# Power.net
KiCad netlist of a schematic drawn in Altium Designer
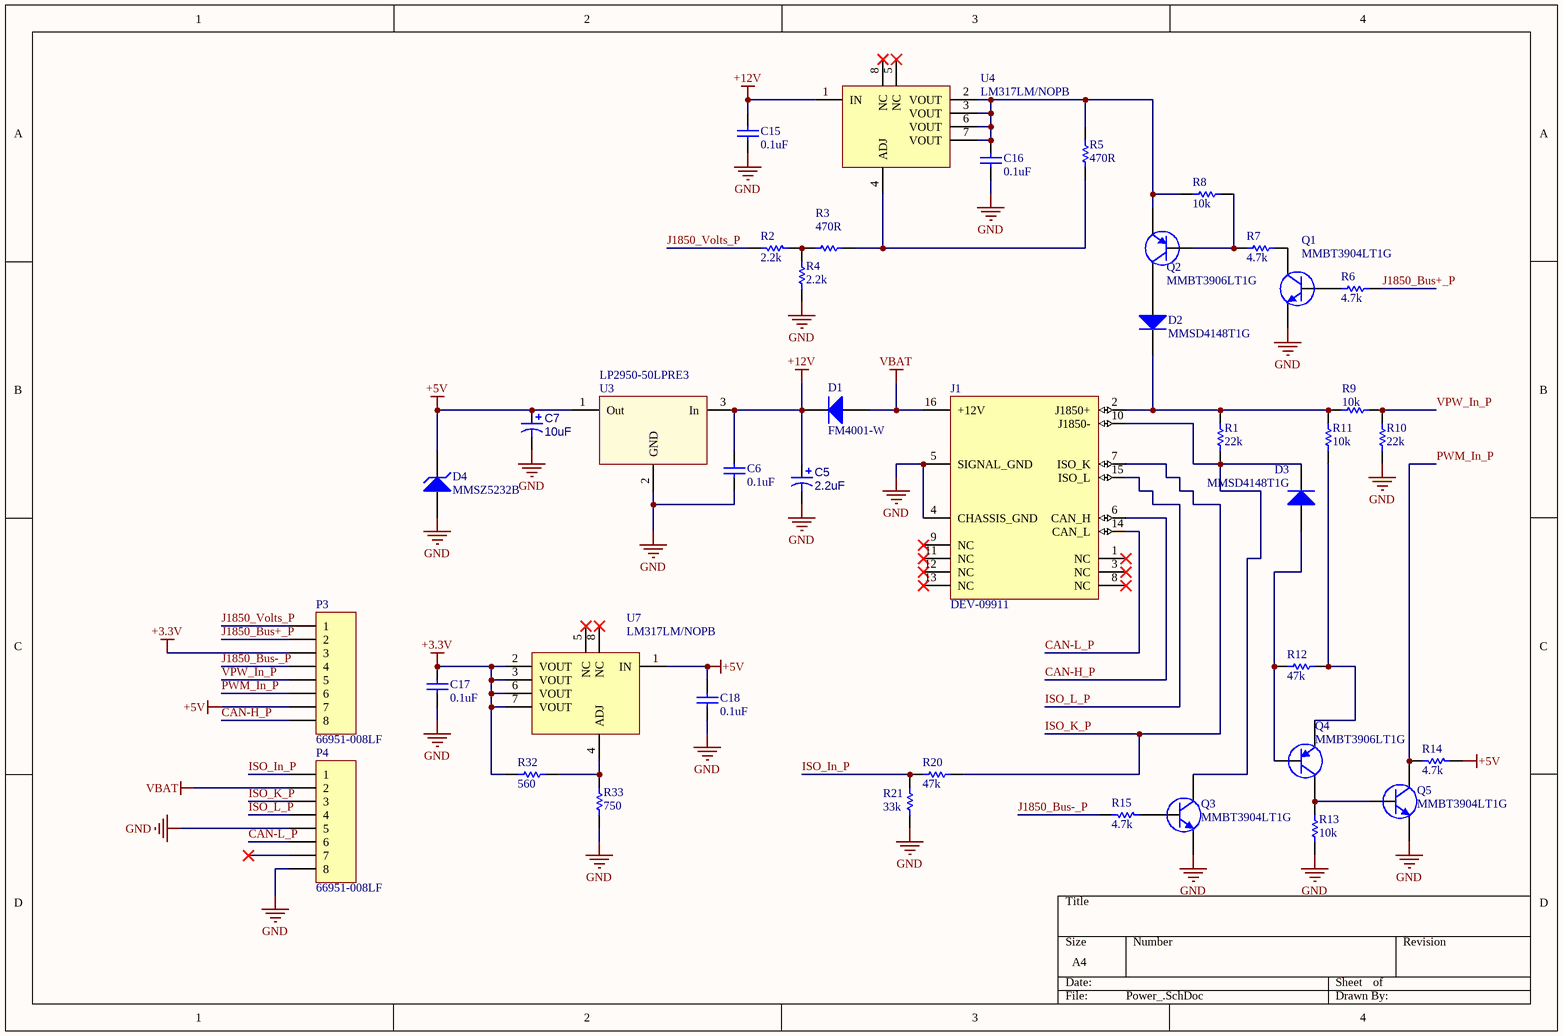
[diagram p0: Power_.SchDoc]

(export (version "E")
  (design (tool "Eeschema 10.0.6"))
  (components
    (comp (ref "C5")
      (value "2.2uF")
      (footprint "Panasonic_Ñ")
      (description "CAP ELECT 2.2UF SV 50V SMD")
      (fields (field (name "MANUFACTURER") "Panasonic") (field (name "PARTNUMBER") "EEE-1HA2R2NR"))
      (libsource (lib "OBDII-components") (part "EEE-1HA2R2NR"))
    )
    (comp (ref "C6")
      (value "0.1uF")
      (footprint "1608[0603]")
      (description "Surface-Mount Ceramic Multilayer Capacitor, 0.1uF, 10% Tolerance, 0603 Size, 50V")
      (libsource (lib "OBDII-components") (part "C0603C104K5RACTU"))
    )
    (comp (ref "C7")
      (value "10uF")
      (footprint "Panasonic_B")
      (description "CAP ELECT 10UF SV 10V SMD")
      (fields (field (name "MANUFACTURER") "Panasonic") (field (name "PARTNUMBER") "EEE-1AA100NR"))
      (libsource (lib "OBDII-components") (part "EEE-1AA100NR"))
    )
    (comp (ref "C15")
      (value "0.1uF")
      (footprint "1608[0603]")
      (description "Surface-Mount Ceramic Multilayer Capacitor, 0.1uF, X7R, 10% Tolerance, 0603 Size, 25V")
      (fields (field (name "PUBLISHER") "Altium Limited"))
      (libsource (lib "OBDII-components") (part "CGA3E2X7R1E104K080AA"))
    )
    (comp (ref "C16")
      (value "0.1uF")
      (footprint "1608[0603]")
      (description "Surface-Mount Ceramic Multilayer Capacitor, 0.1uF, X7R, 10% Tolerance, 0603 Size, 25V")
      (fields (field (name "PUBLISHER") "Altium Limited"))
      (libsource (lib "OBDII-components") (part "CGA3E2X7R1E104K080AA"))
    )
    (comp (ref "C17")
      (value "0.1uF")
      (footprint "1608[0603]")
      (description "Surface-Mount Ceramic Multilayer Capacitor, 0.1uF, 10% Tolerance, 0603 Size, 50V")
      (libsource (lib "OBDII-components") (part "C0603C104K5RACTU"))
    )
    (comp (ref "C18")
      (value "0.1uF")
      (footprint "1608[0603]")
      (description "Surface-Mount Ceramic Multilayer Capacitor, 0.1uF, 10% Tolerance, 0603 Size, 50V")
      (libsource (lib "OBDII-components") (part "C0603C104K5RACTU"))
    )
    (comp (ref "D1")
      (value "FM4001-W")
      (footprint "SMA,2.8mm")
      (description "1 Amp 50V  Rectifier")
      (libsource (lib "OBDII-components") (part "FM4001-W"))
    )
    (comp (ref "D2")
      (value "MMSD4148T1G")
      (footprint "SOD123")
      (description "High Conductance Fast Diode")
      (fields
        (field (name "MANUFACTURER") "OnSemi")
        (field (name "PUBLISHER") "Vanteon")
        (field (name "APPROVED") "M. Jablonski")
      )
      (libsource (lib "OBDII-components") (part "MMSD4148T1G"))
    )
    (comp (ref "D3")
      (value "MMSD4148T1G")
      (footprint "SOD123")
      (description "High Conductance Fast Diode")
      (fields
        (field (name "MANUFACTURER") "OnSemi")
        (field (name "PUBLISHER") "Vanteon")
        (field (name "APPROVED") "M. Jablonski")
      )
      (libsource (lib "OBDII-components") (part "MMSD4148T1G"))
    )
    (comp (ref "D4")
      (value "MMSZ5232B")
      (footprint "SOD123")
      (description "Zener Diodes 5.6 Volt 0.5W 5%")
      (libsource (lib "OBDII-components") (part "MMSZ5232B"))
    )
    (comp (ref "J1")
      (value "DEV-09911")
      (footprint "DEV-09911 - II")
      (description "OBD-II Connector")
      (fields (field (name "MANUFACTURER") "SparkFun Electronics"))
      (libsource (lib "OBDII-components") (part "OBDII_DEV-09911"))
    )
    (comp (ref "P3")
      (value "66951-008LF")
      (footprint "HDR1X8")
      (description "Connector, 8-Pin, 2.54 pitch, 1 row")
      (fields (field (name "PUBLISHER") "Altium Limited"))
      (libsource (lib "OBDII-components") (part "66951-008LF"))
    )
    (comp (ref "P4")
      (value "66951-008LF")
      (footprint "HDR1X8")
      (description "Connector, 8-Pin, 2.54 pitch, 1 row")
      (fields (field (name "PUBLISHER") "Altium Limited"))
      (libsource (lib "OBDII-components") (part "66951-008LF"))
    )
    (comp (ref "Q1")
      (value "MMBT3904LT1G")
      (footprint "SOT23")
      (description "NPN 3904 General Purpose Amplifier")
      (fields
        (field (name "MANUFACTURER") "ON Semiconductor")
        (field (name "PUBLISHER") "Vanteon")
        (field (name "APPROVED") "Yes by Implemenation")
      )
      (libsource (lib "OBDII-components") (part "MMBT3904L"))
    )
    (comp (ref "Q2")
      (value "MMBT3906LT1G")
      (footprint "SOT23")
      (description "PNP 3906 General Purpose Amplifier")
      (fields
        (field (name "MANUFACTURER") "ON Semiconductor")
        (field (name "PUBLISHER") "Vanteon")
        (field (name "APPROVED") "Yes by Implemenation")
      )
      (libsource (lib "OBDII-components") (part "MMBT3906L"))
    )
    (comp (ref "Q3")
      (value "MMBT3904LT1G")
      (footprint "SOT23")
      (description "NPN 3904 General Purpose Amplifier")
      (fields
        (field (name "MANUFACTURER") "ON Semiconductor")
        (field (name "PUBLISHER") "Vanteon")
        (field (name "APPROVED") "Yes by Implemenation")
      )
      (libsource (lib "OBDII-components") (part "MMBT3904L"))
    )
    (comp (ref "Q4")
      (value "MMBT3906LT1G")
      (footprint "SOT23")
      (description "PNP 3906 General Purpose Amplifier")
      (fields
        (field (name "MANUFACTURER") "ON Semiconductor")
        (field (name "PUBLISHER") "Vanteon")
        (field (name "APPROVED") "Yes by Implemenation")
      )
      (libsource (lib "OBDII-components") (part "MMBT3906L"))
    )
    (comp (ref "Q5")
      (value "MMBT3904LT1G")
      (footprint "SOT23")
      (description "NPN 3904 General Purpose Amplifier")
      (fields
        (field (name "MANUFACTURER") "ON Semiconductor")
        (field (name "PUBLISHER") "Vanteon")
        (field (name "APPROVED") "Yes by Implemenation")
      )
      (libsource (lib "OBDII-components") (part "MMBT3904L"))
    )
    (comp (ref "R1")
      (value "22k")
      (footprint "ERA-0805")
      (description "Rectangular Thick Film Chip Resistor, 22 kOhm, 0.1% Tolerance, 0805 Size, 0.125 W")
      (libsource (lib "OBDII-components") (part "ERA6AEB223V"))
    )
    (comp (ref "R2")
      (value "2.2k")
      (footprint "ERA-0805")
      (description "Rectangular Thick Film Chip Resistor, 2.2 kOhm, 0.1% Tolerance, 0805 Size, 0.125 W")
      (libsource (lib "OBDII-components") (part "ERA6AEB222V"))
    )
    (comp (ref "R3")
      (value "470R")
      (footprint "ERA-0805")
      (description "Rectangular Thick Film Chip Resistor, 470 Ohm, 0.1% Tolerance, 0805 Size, 0.125 W")
      (libsource (lib "OBDII-components") (part "ERA6AEB471V"))
    )
    (comp (ref "R4")
      (value "2.2k")
      (footprint "ERA-0805")
      (description "Rectangular Thick Film Chip Resistor, 2.2 kOhm, 0.1% Tolerance, 0805 Size, 0.125 W")
      (libsource (lib "OBDII-components") (part "ERA6AEB222V"))
    )
    (comp (ref "R5")
      (value "470R")
      (footprint "ERA-0805")
      (description "Rectangular Thick Film Chip Resistor, 470 Ohm, 0.1% Tolerance, 0805 Size, 0.125 W")
      (libsource (lib "OBDII-components") (part "ERA6AEB471V"))
    )
    (comp (ref "R6")
      (value "4.7k")
      (footprint "ERA-0805")
      (description "Rectangular Thick Film Chip Resistor, 4.7 kOhm, 0.1% Tolerance, 0805 Size, 0.125 W")
      (libsource (lib "OBDII-components") (part "ERA6AEB472V"))
    )
    (comp (ref "R7")
      (value "4.7k")
      (footprint "ERA-0805")
      (description "Rectangular Thick Film Chip Resistor, 4.7 kOhm, 0.1% Tolerance, 0805 Size, 0.125 W")
      (libsource (lib "OBDII-components") (part "ERA6AEB472V"))
    )
    (comp (ref "R8")
      (value "10k")
      (footprint "ERA-0805")
      (description "Rectangular Thick Film Chip Resistor, 10 kOhm, 0.1% Tolerance, 0805 Size, 0.125 W")
      (libsource (lib "OBDII-components") (part "ERA6AEB103V"))
    )
    (comp (ref "R9")
      (value "10k")
      (footprint "ERA-0805")
      (description "Rectangular Thick Film Chip Resistor, 10 kOhm, 0.1% Tolerance, 0805 Size, 0.125 W")
      (libsource (lib "OBDII-components") (part "ERA6AEB103V"))
    )
    (comp (ref "R10")
      (value "22k")
      (footprint "ERA-0805")
      (description "Rectangular Thick Film Chip Resistor, 22 kOhm, 0.1% Tolerance, 0805 Size, 0.125 W")
      (libsource (lib "OBDII-components") (part "ERA6AEB223V"))
    )
    (comp (ref "R11")
      (value "10k")
      (footprint "ERA-0805")
      (description "Rectangular Thick Film Chip Resistor, 10 kOhm, 0.1% Tolerance, 0805 Size, 0.125 W")
      (libsource (lib "OBDII-components") (part "ERA6AEB103V"))
    )
    (comp (ref "R12")
      (value "47k")
      (footprint "ERA-0805")
      (description "Rectangular Thick Film Chip Resistor, 47 kOhm, 0.1% Tolerance, 0805 Size, 0.125 W")
      (libsource (lib "OBDII-components") (part "ERA6AEB473V"))
    )
    (comp (ref "R13")
      (value "10k")
      (footprint "ERA-0805")
      (description "Rectangular Thick Film Chip Resistor, 10 kOhm, 0.1% Tolerance, 0805 Size, 0.125 W")
      (libsource (lib "OBDII-components") (part "ERA6AEB103V"))
    )
    (comp (ref "R14")
      (value "4.7k")
      (footprint "ERA-0805")
      (description "Rectangular Thick Film Chip Resistor, 4.7 kOhm, 0.1% Tolerance, 0805 Size, 0.125 W")
      (libsource (lib "OBDII-components") (part "ERA6AEB472V"))
    )
    (comp (ref "R15")
      (value "4.7k")
      (footprint "ERA-0805")
      (description "Rectangular Thick Film Chip Resistor, 4.7 kOhm, 0.1% Tolerance, 0805 Size, 0.125 W")
      (libsource (lib "OBDII-components") (part "ERA6AEB472V"))
    )
    (comp (ref "R20")
      (value "47k")
      (footprint "ERA-0805")
      (description "Rectangular Thick Film Chip Resistor, 47 kOhm, 0.1% Tolerance, 0805 Size, 0.125 W")
      (libsource (lib "OBDII-components") (part "ERA6AEB473V"))
    )
    (comp (ref "R21")
      (value "33k")
      (footprint "ERA-0805")
      (description "Rectangular Thick Film Chip Resistor, 33 kOhm, 0.1% Tolerance, 0805 Size, 0.125 W")
      (libsource (lib "OBDII-components") (part "ERA6AEB333V"))
    )
    (comp (ref "R32")
      (value "560")
      (footprint "ERA-0805")
      (description "Rectangular Thick Film Chip Resistor, 560 Ohm, 1% Tolerance, 0805 Size, 0.125 W")
      (libsource (lib "OBDII-components") (part "ERJ6ENF5600V"))
    )
    (comp (ref "R33")
      (value "750")
      (footprint "ERA-0805")
      (description "Rectangular Thick Film Chip Resistor, 750 Ohm, 1% Tolerance, 0805 Size, 0.125 W")
      (libsource (lib "OBDII-components") (part "ERJ6ENF7500V"))
    )
    (comp (ref "U3")
      (value "LP2950-50LPRE3")
      (footprint "TO-92")
      (description "Adjustable Micropower Voltage Regulator With Shutdown; 5V; 100 mA")
      (libsource (lib "OBDII-components") (part "LP2950-50LPRE3"))
    )
    (comp (ref "U4")
      (value "LM317LM/NOPB")
      (footprint "SOIC8N")
      (description "3-terminal adjustable regulator in SO8")
      (fields
        (field (name "MANUFACTURER") "National Semiconductor")
        (field (name "PUBLISHER") "Vanteon")
        (field (name "APPROVED") "Yes by Implementation")
      )
      (libsource (lib "OBDII-components") (part "LM317LM"))
    )
    (comp (ref "U7")
      (value "LM317LM/NOPB")
      (footprint "SOIC8N")
      (description "3-terminal adjustable regulator in SO8")
      (fields
        (field (name "MANUFACTURER") "National Semiconductor")
        (field (name "PUBLISHER") "Vanteon")
        (field (name "APPROVED") "Yes by Implementation")
      )
      (libsource (lib "") (part "LM317LM_1"))
    )
  )
  (nets
    (net (code "1") (name "+3.3V") (class "Default")
      (node (ref "C17") (pin "2") (pinfunction "2_2") (pintype "passive"))
      (node (ref "P3") (pin "3") (pinfunction "3_3") (pintype "passive"))
      (node (ref "R32") (pin "1") (pinfunction "1_1") (pintype "passive"))
      (node (ref "U7") (pin "2") (pinfunction "VOUT_2") (pintype "passive"))
      (node (ref "U7") (pin "3") (pinfunction "VOUT_3") (pintype "passive"))
      (node (ref "U7") (pin "6") (pinfunction "VOUT_6") (pintype "passive"))
      (node (ref "U7") (pin "7") (pinfunction "VOUT_7") (pintype "passive"))
    )
    (net (code "2") (name "+5V") (class "Default")
      (node (ref "C18") (pin "2") (pinfunction "2_2") (pintype "passive"))
      (node (ref "C7") (pin "1") (pinfunction "1_1") (pintype "passive"))
      (node (ref "D4") (pin "1") (pinfunction "K_1") (pintype "passive"))
      (node (ref "P3") (pin "7") (pinfunction "7_7") (pintype "passive"))
      (node (ref "R14") (pin "1") (pinfunction "1_1") (pintype "passive"))
      (node (ref "U3") (pin "1") (pinfunction "Out_1") (pintype "power_in"))
      (node (ref "U7") (pin "1") (pinfunction "IN_1") (pintype "power_in"))
    )
    (net (code "3") (name "+12V") (class "Default")
      (node (ref "C15") (pin "2") (pinfunction "2_2") (pintype "passive"))
      (node (ref "C5") (pin "1") (pinfunction "1_1") (pintype "passive"))
      (node (ref "C6") (pin "2") (pinfunction "2_2") (pintype "passive"))
      (node (ref "D1") (pin "2") (pinfunction "K_2") (pintype "passive"))
      (node (ref "U3") (pin "3") (pinfunction "In_3") (pintype "power_in"))
      (node (ref "U4") (pin "1") (pinfunction "IN_1") (pintype "power_in"))
    )
    (net (code "4") (name "/CAN-H_P") (class "Default")
      (node (ref "J1") (pin "6") (pinfunction "CAN_H_6") (pintype "bidirectional"))
      (node (ref "P3") (pin "8") (pinfunction "8_8") (pintype "passive"))
    )
    (net (code "5") (name "/CAN-L_P") (class "Default")
      (node (ref "J1") (pin "14") (pinfunction "CAN_L_14") (pintype "bidirectional"))
      (node (ref "P4") (pin "6") (pinfunction "6_6") (pintype "passive"))
    )
    (net (code "6") (name "/ISO_In_P") (class "Default")
      (node (ref "P4") (pin "1") (pinfunction "1_1") (pintype "passive"))
      (node (ref "R20") (pin "1") (pinfunction "1_1") (pintype "passive"))
      (node (ref "R21") (pin "2") (pinfunction "2_2") (pintype "passive"))
    )
    (net (code "7") (name "/ISO_K_P") (class "Default")
      (node (ref "J1") (pin "7") (pinfunction "ISO_K_7") (pintype "bidirectional"))
      (node (ref "P4") (pin "3") (pinfunction "3_3") (pintype "passive"))
      (node (ref "R20") (pin "2") (pinfunction "2_2") (pintype "passive"))
    )
    (net (code "8") (name "/ISO_L_P") (class "Default")
      (node (ref "J1") (pin "15") (pinfunction "ISO_L_15") (pintype "bidirectional"))
      (node (ref "P4") (pin "4") (pinfunction "4_4") (pintype "passive"))
    )
    (net (code "9") (name "/J1850_Bus+_P") (class "Default")
      (node (ref "P3") (pin "2") (pinfunction "2_2") (pintype "passive"))
      (node (ref "R6") (pin "2") (pinfunction "2_2") (pintype "passive"))
    )
    (net (code "10") (name "/J1850_Bus-_P") (class "Default")
      (node (ref "P3") (pin "4") (pinfunction "4_4") (pintype "passive"))
      (node (ref "R15") (pin "2") (pinfunction "2_2") (pintype "passive"))
    )
    (net (code "11") (name "/J1850_Volts_P") (class "Default")
      (node (ref "P3") (pin "1") (pinfunction "1_1") (pintype "passive"))
      (node (ref "R2") (pin "2") (pinfunction "2_2") (pintype "passive"))
    )
    (net (code "12") (name "/PWM_In_P") (class "Default")
      (node (ref "P3") (pin "6") (pinfunction "6_6") (pintype "passive"))
      (node (ref "Q5") (pin "3") (pinfunction "C_3") (pintype "passive"))
      (node (ref "R14") (pin "2") (pinfunction "2_2") (pintype "passive"))
    )
    (net (code "13") (name "/VPW_In_P") (class "Default")
      (node (ref "P3") (pin "5") (pinfunction "5_5") (pintype "passive"))
      (node (ref "R10") (pin "2") (pinfunction "2_2") (pintype "passive"))
      (node (ref "R9") (pin "1") (pinfunction "1_1") (pintype "passive"))
    )
    (net (code "14") (name "GND") (class "Default")
      (node (ref "C15") (pin "1") (pinfunction "1_1") (pintype "passive"))
      (node (ref "C16") (pin "1") (pinfunction "1_1") (pintype "passive"))
      (node (ref "C17") (pin "1") (pinfunction "1_1") (pintype "passive"))
      (node (ref "C18") (pin "1") (pinfunction "1_1") (pintype "passive"))
      (node (ref "C5") (pin "2") (pinfunction "2_2") (pintype "passive"))
      (node (ref "C6") (pin "1") (pinfunction "1_1") (pintype "passive"))
      (node (ref "C7") (pin "2") (pinfunction "2_2") (pintype "passive"))
      (node (ref "D4") (pin "2") (pinfunction "A_2") (pintype "passive"))
      (node (ref "J1") (pin "4") (pinfunction "CHASSIS_GND_4") (pintype "power_in"))
      (node (ref "J1") (pin "5") (pinfunction "SIGNAL_GND_5") (pintype "power_in"))
      (node (ref "P4") (pin "5") (pinfunction "5_5") (pintype "passive"))
      (node (ref "P4") (pin "8") (pinfunction "8_8") (pintype "passive"))
      (node (ref "Q1") (pin "2") (pinfunction "E_2") (pintype "passive"))
      (node (ref "Q3") (pin "2") (pinfunction "E_2") (pintype "passive"))
      (node (ref "Q5") (pin "2") (pinfunction "E_2") (pintype "passive"))
      (node (ref "R10") (pin "1") (pinfunction "1_1") (pintype "passive"))
      (node (ref "R13") (pin "2") (pinfunction "2_2") (pintype "passive"))
      (node (ref "R21") (pin "1") (pinfunction "1_1") (pintype "passive"))
      (node (ref "R33") (pin "1") (pinfunction "1_1") (pintype "passive"))
      (node (ref "R4") (pin "1") (pinfunction "1_1") (pintype "passive"))
      (node (ref "U3") (pin "2") (pinfunction "GND_2") (pintype "power_in"))
    )
    (net (code "15") (name "Net-(D2-A)") (class "Default")
      (node (ref "D2") (pin "1") (pinfunction "A_1") (pintype "passive"))
      (node (ref "Q2") (pin "3") (pinfunction "C_3") (pintype "passive"))
    )
    (net (code "16") (name "Net-(D2-C)") (class "Default")
      (node (ref "D2") (pin "2") (pinfunction "C_2") (pintype "passive"))
      (node (ref "J1") (pin "2") (pinfunction "J1850+_2") (pintype "bidirectional"))
      (node (ref "R1") (pin "2") (pinfunction "2_2") (pintype "passive"))
      (node (ref "R11") (pin "1") (pinfunction "1_1") (pintype "passive"))
      (node (ref "R9") (pin "2") (pinfunction "2_2") (pintype "passive"))
    )
    (net (code "17") (name "Net-(D3-A)") (class "Default")
      (node (ref "D3") (pin "1") (pinfunction "A_1") (pintype "passive"))
      (node (ref "Q4") (pin "1") (pinfunction "B_1") (pintype "passive"))
      (node (ref "R12") (pin "1") (pinfunction "1_1") (pintype "passive"))
    )
    (net (code "18") (name "Net-(D3-C)") (class "Default")
      (node (ref "D3") (pin "2") (pinfunction "C_2") (pintype "passive"))
      (node (ref "J1") (pin "10") (pinfunction "J1850-_10") (pintype "bidirectional"))
      (node (ref "Q3") (pin "3") (pinfunction "C_3") (pintype "passive"))
      (node (ref "R1") (pin "1") (pinfunction "1_1") (pintype "passive"))
    )
    (net (code "19") (name "Net-(Q1-B)") (class "Default")
      (node (ref "Q1") (pin "1") (pinfunction "B_1") (pintype "passive"))
      (node (ref "R6") (pin "1") (pinfunction "1_1") (pintype "passive"))
    )
    (net (code "20") (name "Net-(Q1-C)") (class "Default")
      (node (ref "Q1") (pin "3") (pinfunction "C_3") (pintype "passive"))
      (node (ref "R7") (pin "2") (pinfunction "2_2") (pintype "passive"))
    )
    (net (code "21") (name "Net-(Q2-B)") (class "Default")
      (node (ref "Q2") (pin "1") (pinfunction "B_1") (pintype "passive"))
      (node (ref "R7") (pin "1") (pinfunction "1_1") (pintype "passive"))
      (node (ref "R8") (pin "1") (pinfunction "1_1") (pintype "passive"))
    )
    (net (code "22") (name "Net-(Q2-E)") (class "Default")
      (node (ref "C16") (pin "2") (pinfunction "2_2") (pintype "passive"))
      (node (ref "Q2") (pin "2") (pinfunction "E_2") (pintype "passive"))
      (node (ref "R5") (pin "2") (pinfunction "2_2") (pintype "passive"))
      (node (ref "R8") (pin "2") (pinfunction "2_2") (pintype "passive"))
      (node (ref "U4") (pin "2") (pinfunction "VOUT_2") (pintype "passive"))
      (node (ref "U4") (pin "3") (pinfunction "VOUT_3") (pintype "passive"))
      (node (ref "U4") (pin "6") (pinfunction "VOUT_6") (pintype "passive"))
      (node (ref "U4") (pin "7") (pinfunction "VOUT_7") (pintype "passive"))
    )
    (net (code "23") (name "Net-(Q3-B)") (class "Default")
      (node (ref "Q3") (pin "1") (pinfunction "B_1") (pintype "passive"))
      (node (ref "R15") (pin "1") (pinfunction "1_1") (pintype "passive"))
    )
    (net (code "24") (name "Net-(Q4-C)") (class "Default")
      (node (ref "Q4") (pin "3") (pinfunction "C_3") (pintype "passive"))
      (node (ref "Q5") (pin "1") (pinfunction "B_1") (pintype "passive"))
      (node (ref "R13") (pin "1") (pinfunction "1_1") (pintype "passive"))
    )
    (net (code "25") (name "Net-(Q4-E)") (class "Default")
      (node (ref "Q4") (pin "2") (pinfunction "E_2") (pintype "passive"))
      (node (ref "R11") (pin "2") (pinfunction "2_2") (pintype "passive"))
      (node (ref "R12") (pin "2") (pinfunction "2_2") (pintype "passive"))
    )
    (net (code "26") (name "Net-(R2-Pad1)") (class "Default")
      (node (ref "R2") (pin "1") (pinfunction "1_1") (pintype "passive"))
      (node (ref "R3") (pin "2") (pinfunction "2_2") (pintype "passive"))
      (node (ref "R4") (pin "2") (pinfunction "2_2") (pintype "passive"))
    )
    (net (code "27") (name "Net-(U4-ADJ)") (class "Default")
      (node (ref "R3") (pin "1") (pinfunction "1_1") (pintype "passive"))
      (node (ref "R5") (pin "1") (pinfunction "1_1") (pintype "passive"))
      (node (ref "U4") (pin "4") (pinfunction "ADJ_4") (pintype "power_in"))
    )
    (net (code "28") (name "Net-(U7-ADJ)") (class "Default")
      (node (ref "R32") (pin "2") (pinfunction "2_2") (pintype "passive"))
      (node (ref "R33") (pin "2") (pinfunction "2_2") (pintype "passive"))
      (node (ref "U7") (pin "4") (pinfunction "ADJ_4") (pintype "power_in"))
    )
    (net (code "29") (name "VBAT") (class "Default")
      (node (ref "D1") (pin "1") (pinfunction "A_1") (pintype "passive"))
      (node (ref "J1") (pin "16") (pinfunction "+12V_16") (pintype "power_in"))
      (node (ref "P4") (pin "2") (pinfunction "2_2") (pintype "passive"))
    )
    (net (code "30") (name "unconnected-(J1-NC-Pad1)") (class "Default")
      (node (ref "J1") (pin "1") (pinfunction "NC_1") (pintype "passive+no_connect"))
    )
    (net (code "31") (name "unconnected-(J1-NC-Pad3)") (class "Default")
      (node (ref "J1") (pin "3") (pinfunction "NC_3") (pintype "passive+no_connect"))
    )
    (net (code "32") (name "unconnected-(J1-NC-Pad8)") (class "Default")
      (node (ref "J1") (pin "8") (pinfunction "NC_8") (pintype "passive+no_connect"))
    )
    (net (code "33") (name "unconnected-(J1-NC-Pad9)") (class "Default")
      (node (ref "J1") (pin "9") (pinfunction "NC_9") (pintype "passive+no_connect"))
    )
    (net (code "34") (name "unconnected-(J1-NC-Pad11)") (class "Default")
      (node (ref "J1") (pin "11") (pinfunction "NC_11") (pintype "passive+no_connect"))
    )
    (net (code "35") (name "unconnected-(J1-NC-Pad12)") (class "Default")
      (node (ref "J1") (pin "12") (pinfunction "NC_12") (pintype "passive+no_connect"))
    )
    (net (code "36") (name "unconnected-(J1-NC-Pad13)") (class "Default")
      (node (ref "J1") (pin "13") (pinfunction "NC_13") (pintype "passive+no_connect"))
    )
    (net (code "37") (name "unconnected-(P4-Pad7)") (class "Default")
      (node (ref "P4") (pin "7") (pinfunction "7_7") (pintype "passive+no_connect"))
    )
    (net (code "38") (name "unconnected-(U4-NC-Pad5)") (class "Default")
      (node (ref "U4") (pin "5") (pinfunction "NC_5") (pintype "passive+no_connect"))
    )
    (net (code "39") (name "unconnected-(U4-NC-Pad8)") (class "Default")
      (node (ref "U4") (pin "8") (pinfunction "NC_8") (pintype "passive+no_connect"))
    )
    (net (code "40") (name "unconnected-(U7-NC-Pad5)") (class "Default")
      (node (ref "U7") (pin "5") (pinfunction "NC_5") (pintype "passive+no_connect"))
    )
    (net (code "41") (name "unconnected-(U7-NC-Pad8)") (class "Default")
      (node (ref "U7") (pin "8") (pinfunction "NC_8") (pintype "passive+no_connect"))
    )
  )
)
